# spacepwr.net
KiCad netlist of a schematic drawn in EAGLE
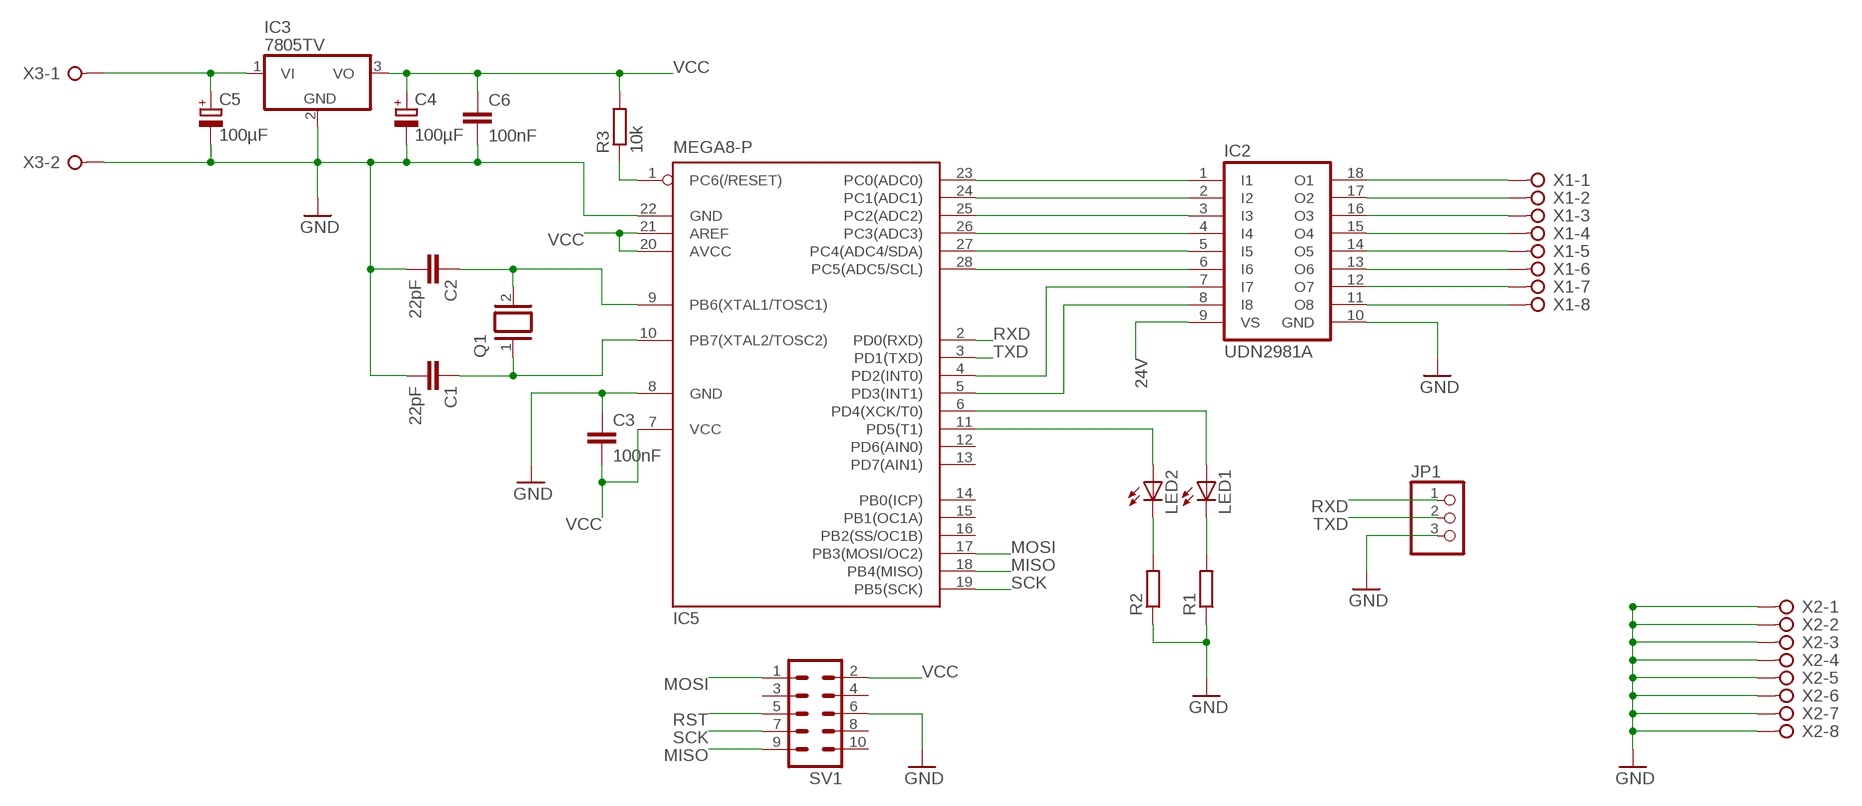
[diagram p0: schematic, sheet 1]

(export (version "E")
  (design (tool "Eeschema 10.0.6"))
  (components
    (comp (ref "C1")
      (value "22pF")
      (footprint "eagle-import:C025-030X050")
      (libsource (lib "eagle-import") (part "C-EU025-030X050"))
    )
    (comp (ref "C2")
      (value "22pF")
      (footprint "eagle-import:C025-030X050")
      (libsource (lib "eagle-import") (part "C-EU025-030X050"))
    )
    (comp (ref "C3")
      (value "100nF")
      (footprint "eagle-import:C025-030X050")
      (libsource (lib "eagle-import") (part "C-EU025-030X050"))
    )
    (comp (ref "C4")
      (value "100µF")
      (footprint "eagle-import:E5-10,5")
      (libsource (lib "eagle-import") (part "CPOL-EUE5-10.5"))
    )
    (comp (ref "C5")
      (value "100µF")
      (footprint "eagle-import:E5-10,5")
      (libsource (lib "eagle-import") (part "CPOL-EUE5-10.5"))
    )
    (comp (ref "C6")
      (value "100nF")
      (footprint "eagle-import:C025-030X050")
      (libsource (lib "eagle-import") (part "C-EU025-030X050"))
    )
    (comp (ref "IC2")
      (value "UDN2981A")
      (footprint "eagle-import:DIL18")
      (libsource (lib "eagle-import") (part "UDN298A1"))
    )
    (comp (ref "IC3")
      (value "7805TV")
      (footprint "eagle-import:TO220V")
      (libsource (lib "eagle-import") (part "78TV05"))
    )
    (comp (ref "IC5")
      (value "MEGA8-P")
      (footprint "eagle-import:DIL28-3")
      (libsource (lib "eagle-import") (part "MEGA8-P"))
    )
    (comp (ref "JP1")
      (value "PINHD-1X3")
      (footprint "eagle-import:1X03")
      (libsource (lib "eagle-import") (part "PINHD-1X3"))
    )
    (comp (ref "LED1")
      (value "LED5MM")
      (footprint "eagle-import:LED5MM")
      (libsource (lib "eagle-import") (part "LED5MM"))
    )
    (comp (ref "LED2")
      (value "LED5MM")
      (footprint "eagle-import:LED5MM")
      (libsource (lib "eagle-import") (part "LED5MM"))
    )
    (comp (ref "Q1")
      (value "XTAL/S")
      (footprint "eagle-import:QS")
      (libsource (lib "eagle-import") (part "XTAL/S"))
    )
    (comp (ref "R1")
      (value "R-EU_0207/10")
      (footprint "eagle-import:0207_10")
      (libsource (lib "eagle-import") (part "R-EU_0207/10"))
    )
    (comp (ref "R2")
      (value "R-EU_0207/10")
      (footprint "eagle-import:0207_10")
      (libsource (lib "eagle-import") (part "R-EU_0207/10"))
    )
    (comp (ref "R3")
      (value "10k")
      (footprint "eagle-import:0207_10")
      (libsource (lib "eagle-import") (part "R-EU_0207/10"))
    )
    (comp (ref "SV1")
      (value "ML10")
      (footprint "eagle-import:ML10")
      (libsource (lib "eagle-import") (part "ML10"))
    )
    (comp (ref "X1")
      (value "W237-08P")
      (footprint "eagle-import:W237-8P")
      (libsource (lib "eagle-import") (part "W237-08P"))
    )
    (comp (ref "X2")
      (value "W237-08P")
      (footprint "eagle-import:W237-8P")
      (fields (field (name "OC_FARNELL") "unknown") (field (name "OC_NEWARK") "unknown"))
      (libsource (lib "eagle-import") (part "W237-08P"))
    )
    (comp (ref "X3")
      (value "W237-02P")
      (footprint "eagle-import:W237-132")
      (libsource (lib "eagle-import") (part "W237-02P"))
    )
  )
  (nets
    (net (code "1") (name "/24V") (class "Default")
      (node (ref "C5") (pin "+") (pinfunction "+_+") (pintype "passive"))
      (node (ref "IC2") (pin "9") (pinfunction "VS_9") (pintype "passive"))
      (node (ref "IC3") (pin "1") (pinfunction "VI_1") (pintype "input"))
      (node (ref "X3") (pin "1") (pinfunction "KL_1") (pintype "passive"))
    )
    (net (code "2") (name "/MISO") (class "Default")
      (node (ref "IC5") (pin "18") (pinfunction "PB4(MISO)_18") (pintype "bidirectional"))
      (node (ref "SV1") (pin "9") (pinfunction "9_9") (pintype "passive"))
    )
    (net (code "3") (name "/MOSI") (class "Default")
      (node (ref "IC5") (pin "17") (pinfunction "PB3(MOSI/OC2)_17") (pintype "bidirectional"))
      (node (ref "SV1") (pin "1") (pinfunction "1_1") (pintype "passive"))
    )
    (net (code "4") (name "/RST") (class "Default")
      (node (ref "IC5") (pin "1") (pinfunction "PC6(/RESET)_1") (pintype "bidirectional"))
      (node (ref "R3") (pin "1") (pinfunction "1_1") (pintype "passive"))
      (node (ref "SV1") (pin "5") (pinfunction "5_5") (pintype "passive"))
    )
    (net (code "5") (name "/RXD") (class "Default")
      (node (ref "IC5") (pin "2") (pinfunction "PD0(RXD)_2") (pintype "bidirectional"))
      (node (ref "JP1") (pin "1") (pinfunction "1_1") (pintype "passive"))
    )
    (net (code "6") (name "/SCK") (class "Default")
      (node (ref "IC5") (pin "19") (pinfunction "PB5(SCK)_19") (pintype "bidirectional"))
      (node (ref "SV1") (pin "7") (pinfunction "7_7") (pintype "passive"))
    )
    (net (code "7") (name "/TXD") (class "Default")
      (node (ref "IC5") (pin "3") (pinfunction "PD1(TXD)_3") (pintype "bidirectional"))
      (node (ref "JP1") (pin "2") (pinfunction "2_2") (pintype "passive"))
    )
    (net (code "8") (name "/VCC") (class "Default")
      (node (ref "C3") (pin "2") (pinfunction "2_2") (pintype "passive"))
      (node (ref "C4") (pin "+") (pinfunction "+_+") (pintype "passive"))
      (node (ref "C6") (pin "1") (pinfunction "1_1") (pintype "passive"))
      (node (ref "IC3") (pin "3") (pinfunction "VO_3") (pintype "passive"))
      (node (ref "IC5") (pin "20") (pinfunction "AVCC_20") (pintype "power_in"))
      (node (ref "IC5") (pin "21") (pinfunction "AREF_21") (pintype "passive"))
      (node (ref "IC5") (pin "7") (pinfunction "VCC_7") (pintype "power_in"))
      (node (ref "R3") (pin "2") (pinfunction "2_2") (pintype "passive"))
      (node (ref "SV1") (pin "2") (pinfunction "2_2") (pintype "passive"))
    )
    (net (code "9") (name "GND") (class "Default")
      (node (ref "C1") (pin "2") (pinfunction "2_2") (pintype "passive"))
      (node (ref "C2") (pin "2") (pinfunction "2_2") (pintype "passive"))
      (node (ref "C3") (pin "1") (pinfunction "1_1") (pintype "passive"))
      (node (ref "C4") (pin "-") (pinfunction "-_-") (pintype "passive"))
      (node (ref "C5") (pin "-") (pinfunction "-_-") (pintype "passive"))
      (node (ref "C6") (pin "2") (pinfunction "2_2") (pintype "passive"))
      (node (ref "IC2") (pin "10") (pinfunction "GND_10") (pintype "power_in"))
      (node (ref "IC3") (pin "2") (pinfunction "GND_2") (pintype "passive"))
      (node (ref "IC5") (pin "22") (pinfunction "GND_22") (pintype "power_in"))
      (node (ref "IC5") (pin "8") (pinfunction "GND_8") (pintype "power_in"))
      (node (ref "JP1") (pin "3") (pinfunction "3_3") (pintype "passive"))
      (node (ref "R1") (pin "1") (pinfunction "1_1") (pintype "passive"))
      (node (ref "R2") (pin "1") (pinfunction "1_1") (pintype "passive"))
      (node (ref "SV1") (pin "6") (pinfunction "6_6") (pintype "passive"))
      (node (ref "X2") (pin "1") (pinfunction "KL_1") (pintype "passive"))
      (node (ref "X2") (pin "2") (pinfunction "KL_2") (pintype "passive"))
      (node (ref "X2") (pin "3") (pinfunction "KL_3") (pintype "passive"))
      (node (ref "X2") (pin "4") (pinfunction "KL_4") (pintype "passive"))
      (node (ref "X2") (pin "5") (pinfunction "KL_5") (pintype "passive"))
      (node (ref "X2") (pin "6") (pinfunction "KL_6") (pintype "passive"))
      (node (ref "X2") (pin "7") (pinfunction "KL_7") (pintype "passive"))
      (node (ref "X2") (pin "8") (pinfunction "KL_8") (pintype "passive"))
      (node (ref "X3") (pin "2") (pinfunction "KL_2") (pintype "passive"))
    )
    (net (code "10") (name "Net-(IC2-I1)") (class "Default")
      (node (ref "IC2") (pin "1") (pinfunction "I1_1") (pintype "input"))
      (node (ref "IC5") (pin "23") (pinfunction "PC0(ADC0)_23") (pintype "bidirectional"))
    )
    (net (code "11") (name "Net-(IC2-I2)") (class "Default")
      (node (ref "IC2") (pin "2") (pinfunction "I2_2") (pintype "input"))
      (node (ref "IC5") (pin "24") (pinfunction "PC1(ADC1)_24") (pintype "bidirectional"))
    )
    (net (code "12") (name "Net-(IC2-I3)") (class "Default")
      (node (ref "IC2") (pin "3") (pinfunction "I3_3") (pintype "input"))
      (node (ref "IC5") (pin "25") (pinfunction "PC2(ADC2)_25") (pintype "bidirectional"))
    )
    (net (code "13") (name "Net-(IC2-I4)") (class "Default")
      (node (ref "IC2") (pin "4") (pinfunction "I4_4") (pintype "input"))
      (node (ref "IC5") (pin "26") (pinfunction "PC3(ADC3)_26") (pintype "bidirectional"))
    )
    (net (code "14") (name "Net-(IC2-I5)") (class "Default")
      (node (ref "IC2") (pin "5") (pinfunction "I5_5") (pintype "input"))
      (node (ref "IC5") (pin "27") (pinfunction "PC4(ADC4/SDA)_27") (pintype "bidirectional"))
    )
    (net (code "15") (name "Net-(IC2-I6)") (class "Default")
      (node (ref "IC2") (pin "6") (pinfunction "I6_6") (pintype "input"))
      (node (ref "IC5") (pin "28") (pinfunction "PC5(ADC5/SCL)_28") (pintype "bidirectional"))
    )
    (net (code "16") (name "Net-(IC2-I7)") (class "Default")
      (node (ref "IC2") (pin "7") (pinfunction "I7_7") (pintype "input"))
      (node (ref "IC5") (pin "4") (pinfunction "PD2(INT0)_4") (pintype "bidirectional"))
    )
    (net (code "17") (name "Net-(IC2-I8)") (class "Default")
      (node (ref "IC2") (pin "8") (pinfunction "I8_8") (pintype "input"))
      (node (ref "IC5") (pin "5") (pinfunction "PD3(INT1)_5") (pintype "bidirectional"))
    )
    (net (code "18") (name "Net-(IC2-O1)") (class "Default")
      (node (ref "IC2") (pin "18") (pinfunction "O1_18") (pintype "open_collector"))
      (node (ref "X1") (pin "1") (pinfunction "KL_1") (pintype "passive"))
    )
    (net (code "19") (name "Net-(IC2-O2)") (class "Default")
      (node (ref "IC2") (pin "17") (pinfunction "O2_17") (pintype "open_collector"))
      (node (ref "X1") (pin "2") (pinfunction "KL_2") (pintype "passive"))
    )
    (net (code "20") (name "Net-(IC2-O3)") (class "Default")
      (node (ref "IC2") (pin "16") (pinfunction "O3_16") (pintype "open_collector"))
      (node (ref "X1") (pin "3") (pinfunction "KL_3") (pintype "passive"))
    )
    (net (code "21") (name "Net-(IC2-O4)") (class "Default")
      (node (ref "IC2") (pin "15") (pinfunction "O4_15") (pintype "open_collector"))
      (node (ref "X1") (pin "4") (pinfunction "KL_4") (pintype "passive"))
    )
    (net (code "22") (name "Net-(IC2-O5)") (class "Default")
      (node (ref "IC2") (pin "14") (pinfunction "O5_14") (pintype "open_collector"))
      (node (ref "X1") (pin "5") (pinfunction "KL_5") (pintype "passive"))
    )
    (net (code "23") (name "Net-(IC2-O6)") (class "Default")
      (node (ref "IC2") (pin "13") (pinfunction "O6_13") (pintype "open_collector"))
      (node (ref "X1") (pin "6") (pinfunction "KL_6") (pintype "passive"))
    )
    (net (code "24") (name "Net-(IC2-O7)") (class "Default")
      (node (ref "IC2") (pin "12") (pinfunction "O7_12") (pintype "open_collector"))
      (node (ref "X1") (pin "7") (pinfunction "KL_7") (pintype "passive"))
    )
    (net (code "25") (name "Net-(IC2-O8)") (class "Default")
      (node (ref "IC2") (pin "11") (pinfunction "O8_11") (pintype "open_collector"))
      (node (ref "X1") (pin "8") (pinfunction "KL_8") (pintype "passive"))
    )
    (net (code "26") (name "Net-(IC5-PB6(XTAL1{slash}TOSC1))") (class "Default")
      (node (ref "C2") (pin "1") (pinfunction "1_1") (pintype "passive"))
      (node (ref "IC5") (pin "9") (pinfunction "PB6(XTAL1/TOSC1)_9") (pintype "bidirectional"))
      (node (ref "Q1") (pin "2") (pinfunction "2_2") (pintype "passive"))
    )
    (net (code "27") (name "Net-(IC5-PB7(XTAL2{slash}TOSC2))") (class "Default")
      (node (ref "C1") (pin "1") (pinfunction "1_1") (pintype "passive"))
      (node (ref "IC5") (pin "10") (pinfunction "PB7(XTAL2/TOSC2)_10") (pintype "bidirectional"))
      (node (ref "Q1") (pin "1") (pinfunction "1_1") (pintype "passive"))
    )
    (net (code "28") (name "Net-(IC5-PD4(XCK{slash}T0))") (class "Default")
      (node (ref "IC5") (pin "6") (pinfunction "PD4(XCK/T0)_6") (pintype "bidirectional"))
      (node (ref "LED1") (pin "A") (pinfunction "A_A") (pintype "passive"))
    )
    (net (code "29") (name "Net-(IC5-PD5(T1))") (class "Default")
      (node (ref "IC5") (pin "11") (pinfunction "PD5(T1)_11") (pintype "bidirectional"))
      (node (ref "LED2") (pin "A") (pinfunction "A_A") (pintype "passive"))
    )
    (net (code "30") (name "Net-(LED1-C)") (class "Default")
      (node (ref "LED1") (pin "K") (pinfunction "C_K") (pintype "passive"))
      (node (ref "R1") (pin "2") (pinfunction "2_2") (pintype "passive"))
    )
    (net (code "31") (name "Net-(LED2-C)") (class "Default")
      (node (ref "LED2") (pin "K") (pinfunction "C_K") (pintype "passive"))
      (node (ref "R2") (pin "2") (pinfunction "2_2") (pintype "passive"))
    )
    (net (code "32") (name "unconnected-(IC5-PB0(ICP)-Pad14)") (class "Default")
      (node (ref "IC5") (pin "14") (pinfunction "PB0(ICP)_14") (pintype "bidirectional"))
    )
    (net (code "33") (name "unconnected-(IC5-PB1(OC1A)-Pad15)") (class "Default")
      (node (ref "IC5") (pin "15") (pinfunction "PB1(OC1A)_15") (pintype "bidirectional"))
    )
    (net (code "34") (name "unconnected-(IC5-PB2(SS{slash}OC1B)-Pad16)") (class "Default")
      (node (ref "IC5") (pin "16") (pinfunction "PB2(SS/OC1B)_16") (pintype "bidirectional"))
    )
    (net (code "35") (name "unconnected-(IC5-PD6(AIN0)-Pad12)") (class "Default")
      (node (ref "IC5") (pin "12") (pinfunction "PD6(AIN0)_12") (pintype "bidirectional"))
    )
    (net (code "36") (name "unconnected-(IC5-PD7(AIN1)-Pad13)") (class "Default")
      (node (ref "IC5") (pin "13") (pinfunction "PD7(AIN1)_13") (pintype "bidirectional"))
    )
    (net (code "37") (name "unconnected-(SV1-Pad3)") (class "Default")
      (node (ref "SV1") (pin "3") (pinfunction "3_3") (pintype "passive"))
    )
    (net (code "38") (name "unconnected-(SV1-Pad4)") (class "Default")
      (node (ref "SV1") (pin "4") (pinfunction "4_4") (pintype "passive"))
    )
    (net (code "39") (name "unconnected-(SV1-Pad8)") (class "Default")
      (node (ref "SV1") (pin "8") (pinfunction "8_8") (pintype "passive"))
    )
    (net (code "40") (name "unconnected-(SV1-Pad10)") (class "Default")
      (node (ref "SV1") (pin "10") (pinfunction "10_10") (pintype "passive"))
    )
  )
)
